# uC.net
KiCad netlist of a schematic drawn in Altium Designer
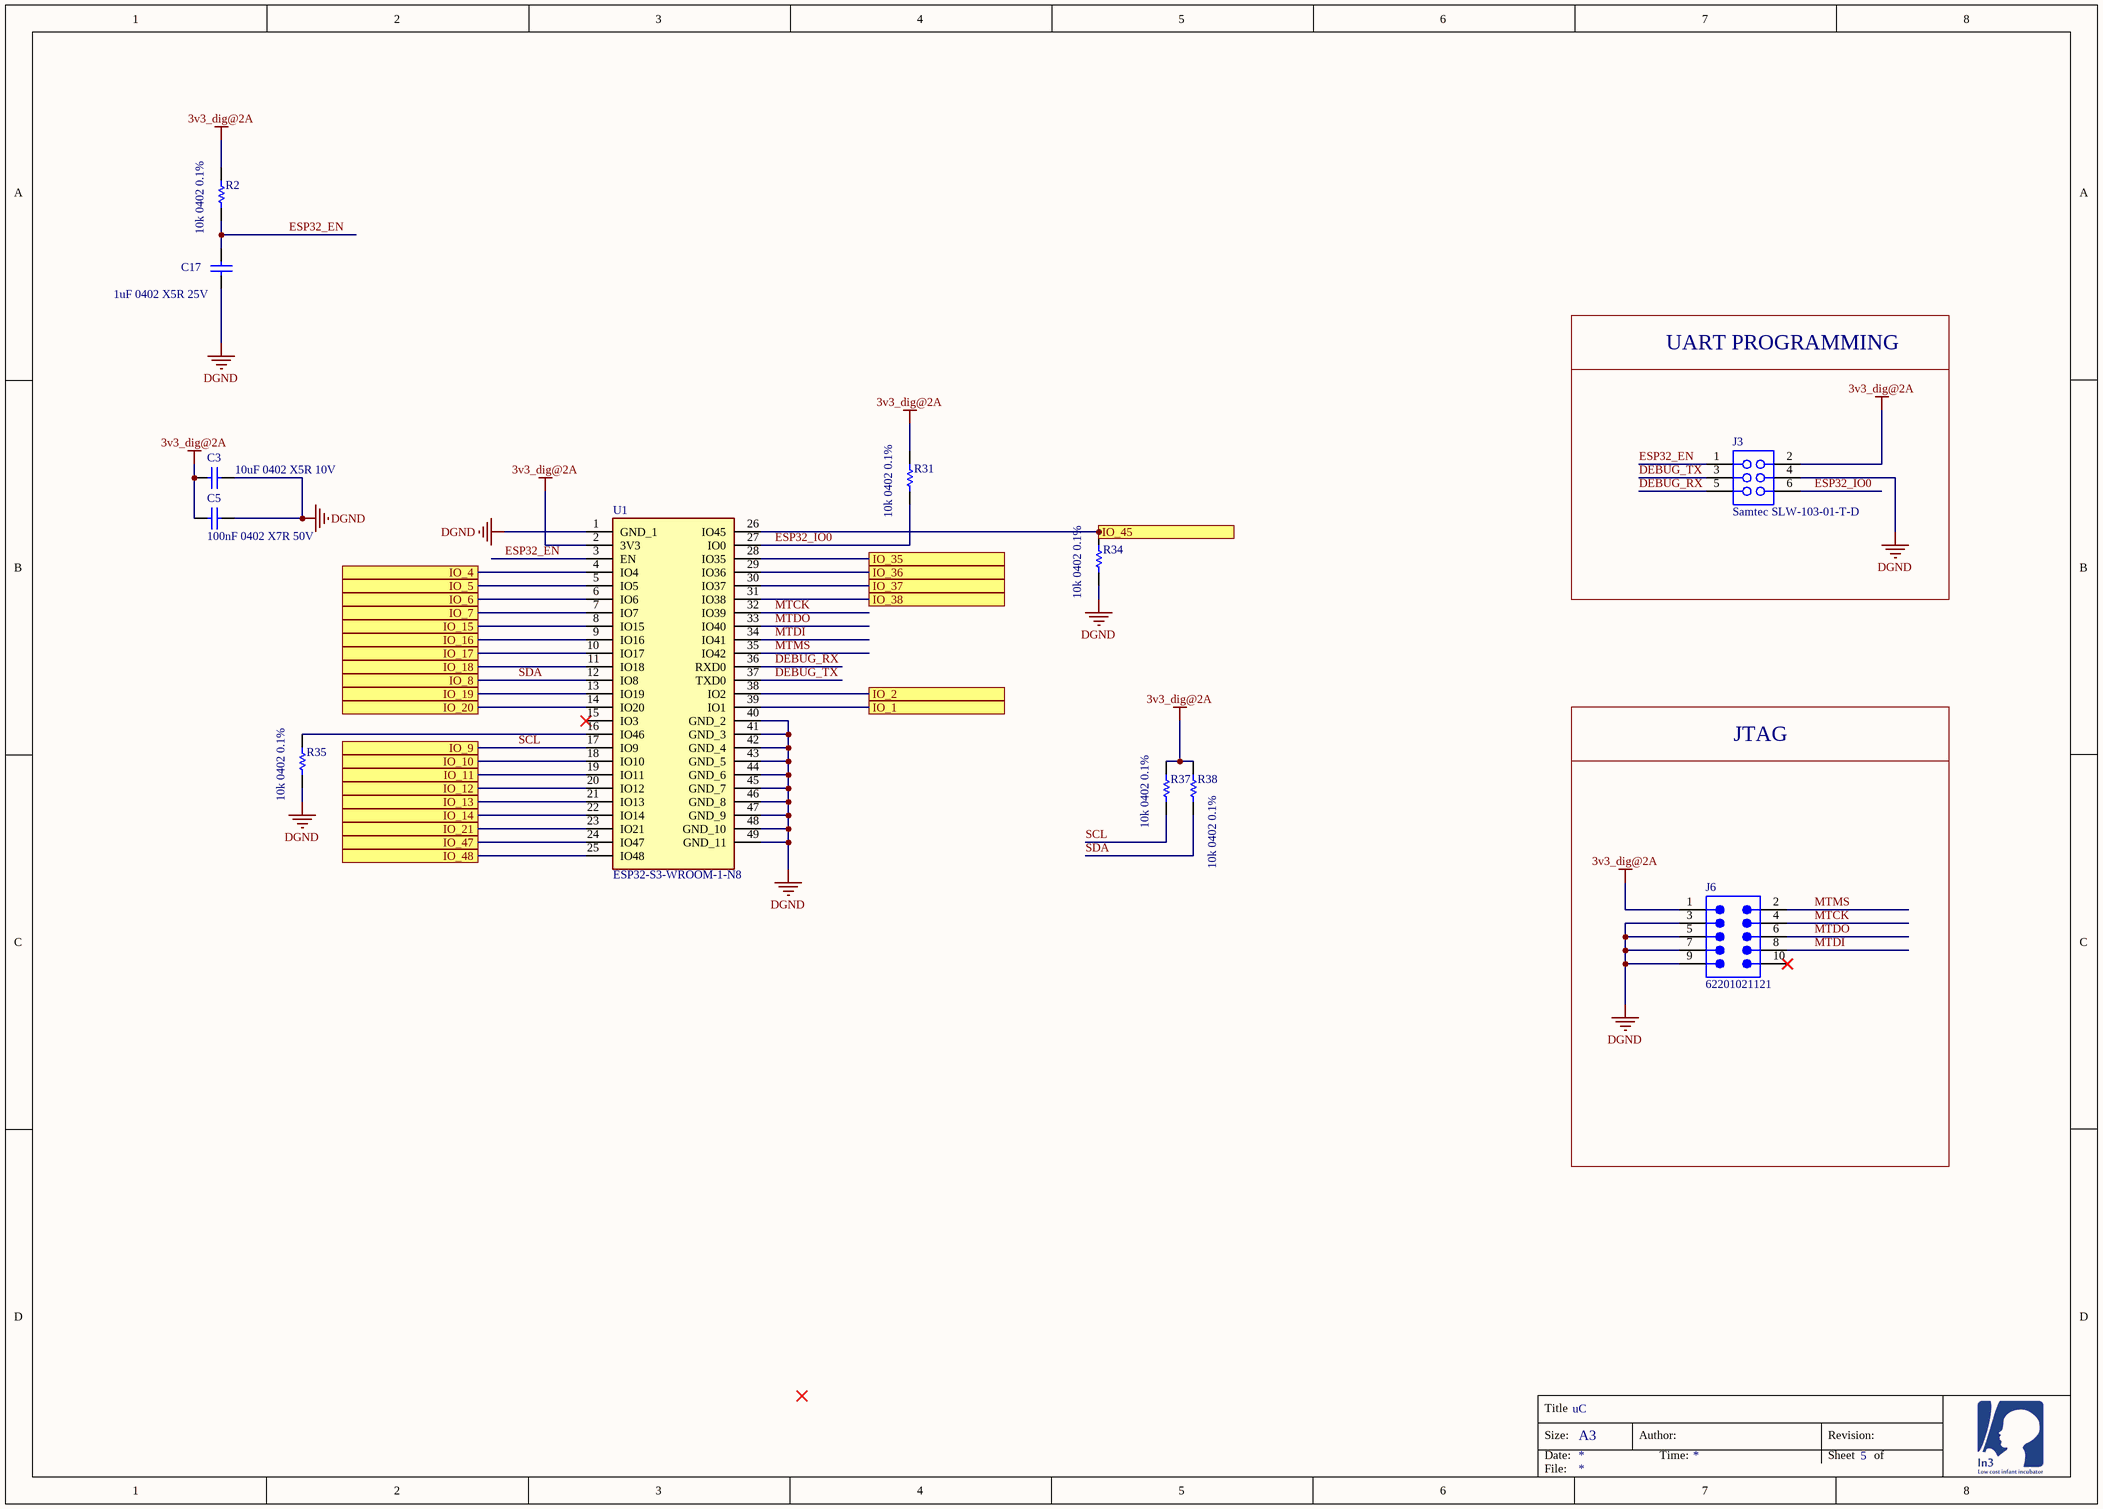
[diagram p0: uC.SchDoc]

(export (version "E")
  (design (tool "Eeschema 10.0.6"))
  (components
    (comp (ref "C3")
      (value "10uF 0402 X5R 10V")
      (footprint "CAPC1005X55X25NL5T10")
      (libsource (lib "Altium Content Vault") (part "CAP-NP-2"))
    )
    (comp (ref "C5")
      (value "100nF 0402 X7R 50V")
      (footprint "CAPC1005X55X25NL5T10")
      (libsource (lib "Altium Content Vault") (part "CAP-NP-2"))
    )
    (comp (ref "C17")
      (value "1uF 0402 X5R 25V")
      (footprint "CAPC1005X55X25NL5T10")
      (libsource (lib "Altium Content Vault") (part "CAP-NP-2"))
    )
    (comp (ref "J3")
      (value "Samtec SLW-103-01-T-D")
      (footprint "PCB-37z8hw1ej4f71bosen9e-1")
      (description "Dual Row Connector Female Samtec SLW-103-01-T-D")
      (fields (field (name "MANUFACTURER PART NUMBER") "SLW-103-01-T-D"))
      (libsource (lib "in3ator") (part "CMP-bcf575fbeff46332-1"))
    )
    (comp (ref "J6")
      (value "62201021121")
      (footprint "62201021121")
      (libsource (lib "Altium Content Vault") (part "Header_Male_2R_10P"))
    )
    (comp (ref "R2")
      (value "10k 0402 0.1%")
      (footprint "RESC1005X40X25ML05T10")
      (libsource (lib "Altium Content Vault") (part "RES"))
    )
    (comp (ref "R31")
      (value "10k 0402 0.1%")
      (footprint "RESC1005X40X25ML05T10")
      (libsource (lib "Altium Content Vault") (part "RES"))
    )
    (comp (ref "R34")
      (value "10k 0402 0.1%")
      (footprint "RESC1005X40X25ML05T10")
      (libsource (lib "Altium Content Vault") (part "RES"))
    )
    (comp (ref "R35")
      (value "10k 0402 0.1%")
      (footprint "RESC1005X40X25ML05T10")
      (libsource (lib "Altium Content Vault") (part "RES"))
    )
    (comp (ref "R37")
      (value "10k 0402 0.1%")
      (footprint "RESC1005X40X25ML05T10")
      (libsource (lib "Altium Content Vault") (part "RES"))
    )
    (comp (ref "R38")
      (value "10k 0402 0.1%")
      (footprint "RESC1005X40X25ML05T10")
      (libsource (lib "Altium Content Vault") (part "RES"))
    )
    (comp (ref "U1")
      (value "ESP32-S3-WROOM-1-N8")
      (footprint "SamacSys:ESP32S3WROOM1N8R2")
      (description "Integrated Circuit")
      (fields (field (name "MOUSER PART NUMBER") "356-ESP32-S3WROOM1N8"))
      (libsource (lib "*") (part "ESP32-S3-WROOM-1-N8"))
    )
  )
  (nets
    (net (code "1") (name "/DEBUG_RX") (class "Default")
      (node (ref "J3") (pin "5") (pinfunction "5_5") (pintype "passive"))
      (node (ref "U1") (pin "36") (pinfunction "RXD0_36") (pintype "passive"))
    )
    (net (code "2") (name "/DEBUG_TX") (class "Default")
      (node (ref "J3") (pin "3") (pinfunction "3_3") (pintype "passive"))
      (node (ref "U1") (pin "37") (pinfunction "TXD0_37") (pintype "passive"))
    )
    (net (code "3") (name "/ESP32_EN") (class "Default")
      (node (ref "C17") (pin "2") (pinfunction "2_2") (pintype "passive"))
      (node (ref "J3") (pin "1") (pinfunction "1_1") (pintype "passive"))
      (node (ref "R2") (pin "1") (pinfunction "1_1") (pintype "passive"))
      (node (ref "U1") (pin "3") (pinfunction "EN_3") (pintype "passive"))
    )
    (net (code "4") (name "/ESP32_IO0") (class "Default")
      (node (ref "J3") (pin "6") (pinfunction "6_6") (pintype "passive"))
      (node (ref "R31") (pin "1") (pinfunction "1_1") (pintype "passive"))
      (node (ref "U1") (pin "27") (pinfunction "IO0_27") (pintype "passive"))
    )
    (net (code "5") (name "/IO_1") (class "Default")
      (node (ref "U1") (pin "39") (pinfunction "IO1_39") (pintype "passive"))
    )
    (net (code "6") (name "/IO_2") (class "Default")
      (node (ref "U1") (pin "38") (pinfunction "IO2_38") (pintype "passive"))
    )
    (net (code "7") (name "/IO_4") (class "Default")
      (node (ref "U1") (pin "4") (pinfunction "IO4_4") (pintype "passive"))
    )
    (net (code "8") (name "/IO_5") (class "Default")
      (node (ref "U1") (pin "5") (pinfunction "IO5_5") (pintype "passive"))
    )
    (net (code "9") (name "/IO_6") (class "Default")
      (node (ref "U1") (pin "6") (pinfunction "IO6_6") (pintype "passive"))
    )
    (net (code "10") (name "/IO_7") (class "Default")
      (node (ref "U1") (pin "7") (pinfunction "IO7_7") (pintype "passive"))
    )
    (net (code "11") (name "/IO_10") (class "Default")
      (node (ref "U1") (pin "18") (pinfunction "IO10_18") (pintype "passive"))
    )
    (net (code "12") (name "/IO_11") (class "Default")
      (node (ref "U1") (pin "19") (pinfunction "IO11_19") (pintype "passive"))
    )
    (net (code "13") (name "/IO_12") (class "Default")
      (node (ref "U1") (pin "20") (pinfunction "IO12_20") (pintype "passive"))
    )
    (net (code "14") (name "/IO_13") (class "Default")
      (node (ref "U1") (pin "21") (pinfunction "IO13_21") (pintype "passive"))
    )
    (net (code "15") (name "/IO_14") (class "Default")
      (node (ref "U1") (pin "22") (pinfunction "IO14_22") (pintype "passive"))
    )
    (net (code "16") (name "/IO_15") (class "Default")
      (node (ref "U1") (pin "8") (pinfunction "IO15_8") (pintype "passive"))
    )
    (net (code "17") (name "/IO_16") (class "Default")
      (node (ref "U1") (pin "9") (pinfunction "IO16_9") (pintype "passive"))
    )
    (net (code "18") (name "/IO_17") (class "Default")
      (node (ref "U1") (pin "10") (pinfunction "IO17_10") (pintype "passive"))
    )
    (net (code "19") (name "/IO_18") (class "Default")
      (node (ref "U1") (pin "11") (pinfunction "IO18_11") (pintype "passive"))
    )
    (net (code "20") (name "/IO_19") (class "Default")
      (node (ref "U1") (pin "13") (pinfunction "IO19_13") (pintype "passive"))
    )
    (net (code "21") (name "/IO_20") (class "Default")
      (node (ref "U1") (pin "14") (pinfunction "IO20_14") (pintype "passive"))
    )
    (net (code "22") (name "/IO_21") (class "Default")
      (node (ref "U1") (pin "23") (pinfunction "IO21_23") (pintype "passive"))
    )
    (net (code "23") (name "/IO_35") (class "Default")
      (node (ref "U1") (pin "28") (pinfunction "IO35_28") (pintype "passive"))
    )
    (net (code "24") (name "/IO_36") (class "Default")
      (node (ref "U1") (pin "29") (pinfunction "IO36_29") (pintype "passive"))
    )
    (net (code "25") (name "/IO_37") (class "Default")
      (node (ref "U1") (pin "30") (pinfunction "IO37_30") (pintype "passive"))
    )
    (net (code "26") (name "/IO_38") (class "Default")
      (node (ref "U1") (pin "31") (pinfunction "IO38_31") (pintype "passive"))
    )
    (net (code "27") (name "/IO_45") (class "Default")
      (node (ref "R34") (pin "2") (pinfunction "2_2") (pintype "passive"))
      (node (ref "U1") (pin "26") (pinfunction "IO45_26") (pintype "passive"))
    )
    (net (code "28") (name "/IO_47") (class "Default")
      (node (ref "U1") (pin "24") (pinfunction "IO47_24") (pintype "passive"))
    )
    (net (code "29") (name "/IO_48") (class "Default")
      (node (ref "U1") (pin "25") (pinfunction "IO48_25") (pintype "passive"))
    )
    (net (code "30") (name "/MTCK") (class "Default")
      (node (ref "J6") (pin "4") (pinfunction "4_4") (pintype "passive"))
      (node (ref "U1") (pin "32") (pinfunction "IO39_32") (pintype "passive"))
    )
    (net (code "31") (name "/MTDI") (class "Default")
      (node (ref "J6") (pin "8") (pinfunction "8_8") (pintype "passive"))
      (node (ref "U1") (pin "34") (pinfunction "IO41_34") (pintype "passive"))
    )
    (net (code "32") (name "/MTDO") (class "Default")
      (node (ref "J6") (pin "6") (pinfunction "6_6") (pintype "passive"))
      (node (ref "U1") (pin "33") (pinfunction "IO40_33") (pintype "passive"))
    )
    (net (code "33") (name "/MTMS") (class "Default")
      (node (ref "J6") (pin "2") (pinfunction "2_2") (pintype "passive"))
      (node (ref "U1") (pin "35") (pinfunction "IO42_35") (pintype "passive"))
    )
    (net (code "34") (name "/SCL") (class "Default")
      (node (ref "R37") (pin "1") (pinfunction "1_1") (pintype "passive"))
      (node (ref "U1") (pin "17") (pinfunction "IO9_17") (pintype "passive"))
    )
    (net (code "35") (name "/SDA") (class "Default")
      (node (ref "R38") (pin "1") (pinfunction "1_1") (pintype "passive"))
      (node (ref "U1") (pin "12") (pinfunction "IO8_12") (pintype "passive"))
    )
    (net (code "36") (name "3v3_dig@2A") (class "Default")
      (node (ref "C3") (pin "2") (pinfunction "2_2") (pintype "passive"))
      (node (ref "C5") (pin "2") (pinfunction "2_2") (pintype "passive"))
      (node (ref "J3") (pin "2") (pinfunction "2_2") (pintype "passive"))
      (node (ref "J6") (pin "1") (pinfunction "1_1") (pintype "passive"))
      (node (ref "R2") (pin "2") (pinfunction "2_2") (pintype "passive"))
      (node (ref "R31") (pin "2") (pinfunction "2_2") (pintype "passive"))
      (node (ref "R37") (pin "2") (pinfunction "2_2") (pintype "passive"))
      (node (ref "R38") (pin "2") (pinfunction "2_2") (pintype "passive"))
      (node (ref "U1") (pin "2") (pinfunction "3V3_2") (pintype "passive"))
    )
    (net (code "37") (name "DGND") (class "Default")
      (node (ref "C17") (pin "1") (pinfunction "1_1") (pintype "passive"))
      (node (ref "C3") (pin "1") (pinfunction "1_1") (pintype "passive"))
      (node (ref "C5") (pin "1") (pinfunction "1_1") (pintype "passive"))
      (node (ref "J3") (pin "4") (pinfunction "4_4") (pintype "passive"))
      (node (ref "J6") (pin "3") (pinfunction "3_3") (pintype "passive"))
      (node (ref "J6") (pin "5") (pinfunction "5_5") (pintype "passive"))
      (node (ref "J6") (pin "7") (pinfunction "7_7") (pintype "passive"))
      (node (ref "J6") (pin "9") (pinfunction "9_9") (pintype "passive"))
      (node (ref "R34") (pin "1") (pinfunction "1_1") (pintype "passive"))
      (node (ref "R35") (pin "1") (pinfunction "1_1") (pintype "passive"))
      (node (ref "U1") (pin "1") (pinfunction "GND_1_1") (pintype "passive"))
      (node (ref "U1") (pin "40") (pinfunction "GND_2_40") (pintype "passive"))
      (node (ref "U1") (pin "41") (pinfunction "GND_3_41") (pintype "passive"))
      (node (ref "U1") (pin "42") (pinfunction "GND_4_42") (pintype "passive"))
      (node (ref "U1") (pin "43") (pinfunction "GND_5_43") (pintype "passive"))
      (node (ref "U1") (pin "44") (pinfunction "GND_6_44") (pintype "passive"))
      (node (ref "U1") (pin "45") (pinfunction "GND_7_45") (pintype "passive"))
      (node (ref "U1") (pin "46") (pinfunction "GND_8_46") (pintype "passive"))
      (node (ref "U1") (pin "47") (pinfunction "GND_9_47") (pintype "passive"))
      (node (ref "U1") (pin "48") (pinfunction "GND_10_48") (pintype "passive"))
      (node (ref "U1") (pin "49") (pinfunction "GND_11_49") (pintype "passive"))
    )
    (net (code "38") (name "Net-(U1-IO46)") (class "Default")
      (node (ref "R35") (pin "2") (pinfunction "2_2") (pintype "passive"))
      (node (ref "U1") (pin "16") (pinfunction "IO46_16") (pintype "passive"))
    )
    (net (code "39") (name "unconnected-(J6-Pad10)") (class "Default")
      (node (ref "J6") (pin "10") (pinfunction "10_10") (pintype "passive+no_connect"))
    )
    (net (code "40") (name "unconnected-(U1-IO3-Pad15)") (class "Default")
      (node (ref "U1") (pin "15") (pinfunction "IO3_15") (pintype "passive+no_connect"))
    )
  )
)
